# design.net
KiCad netlist of a schematic drawn in Altium Designer
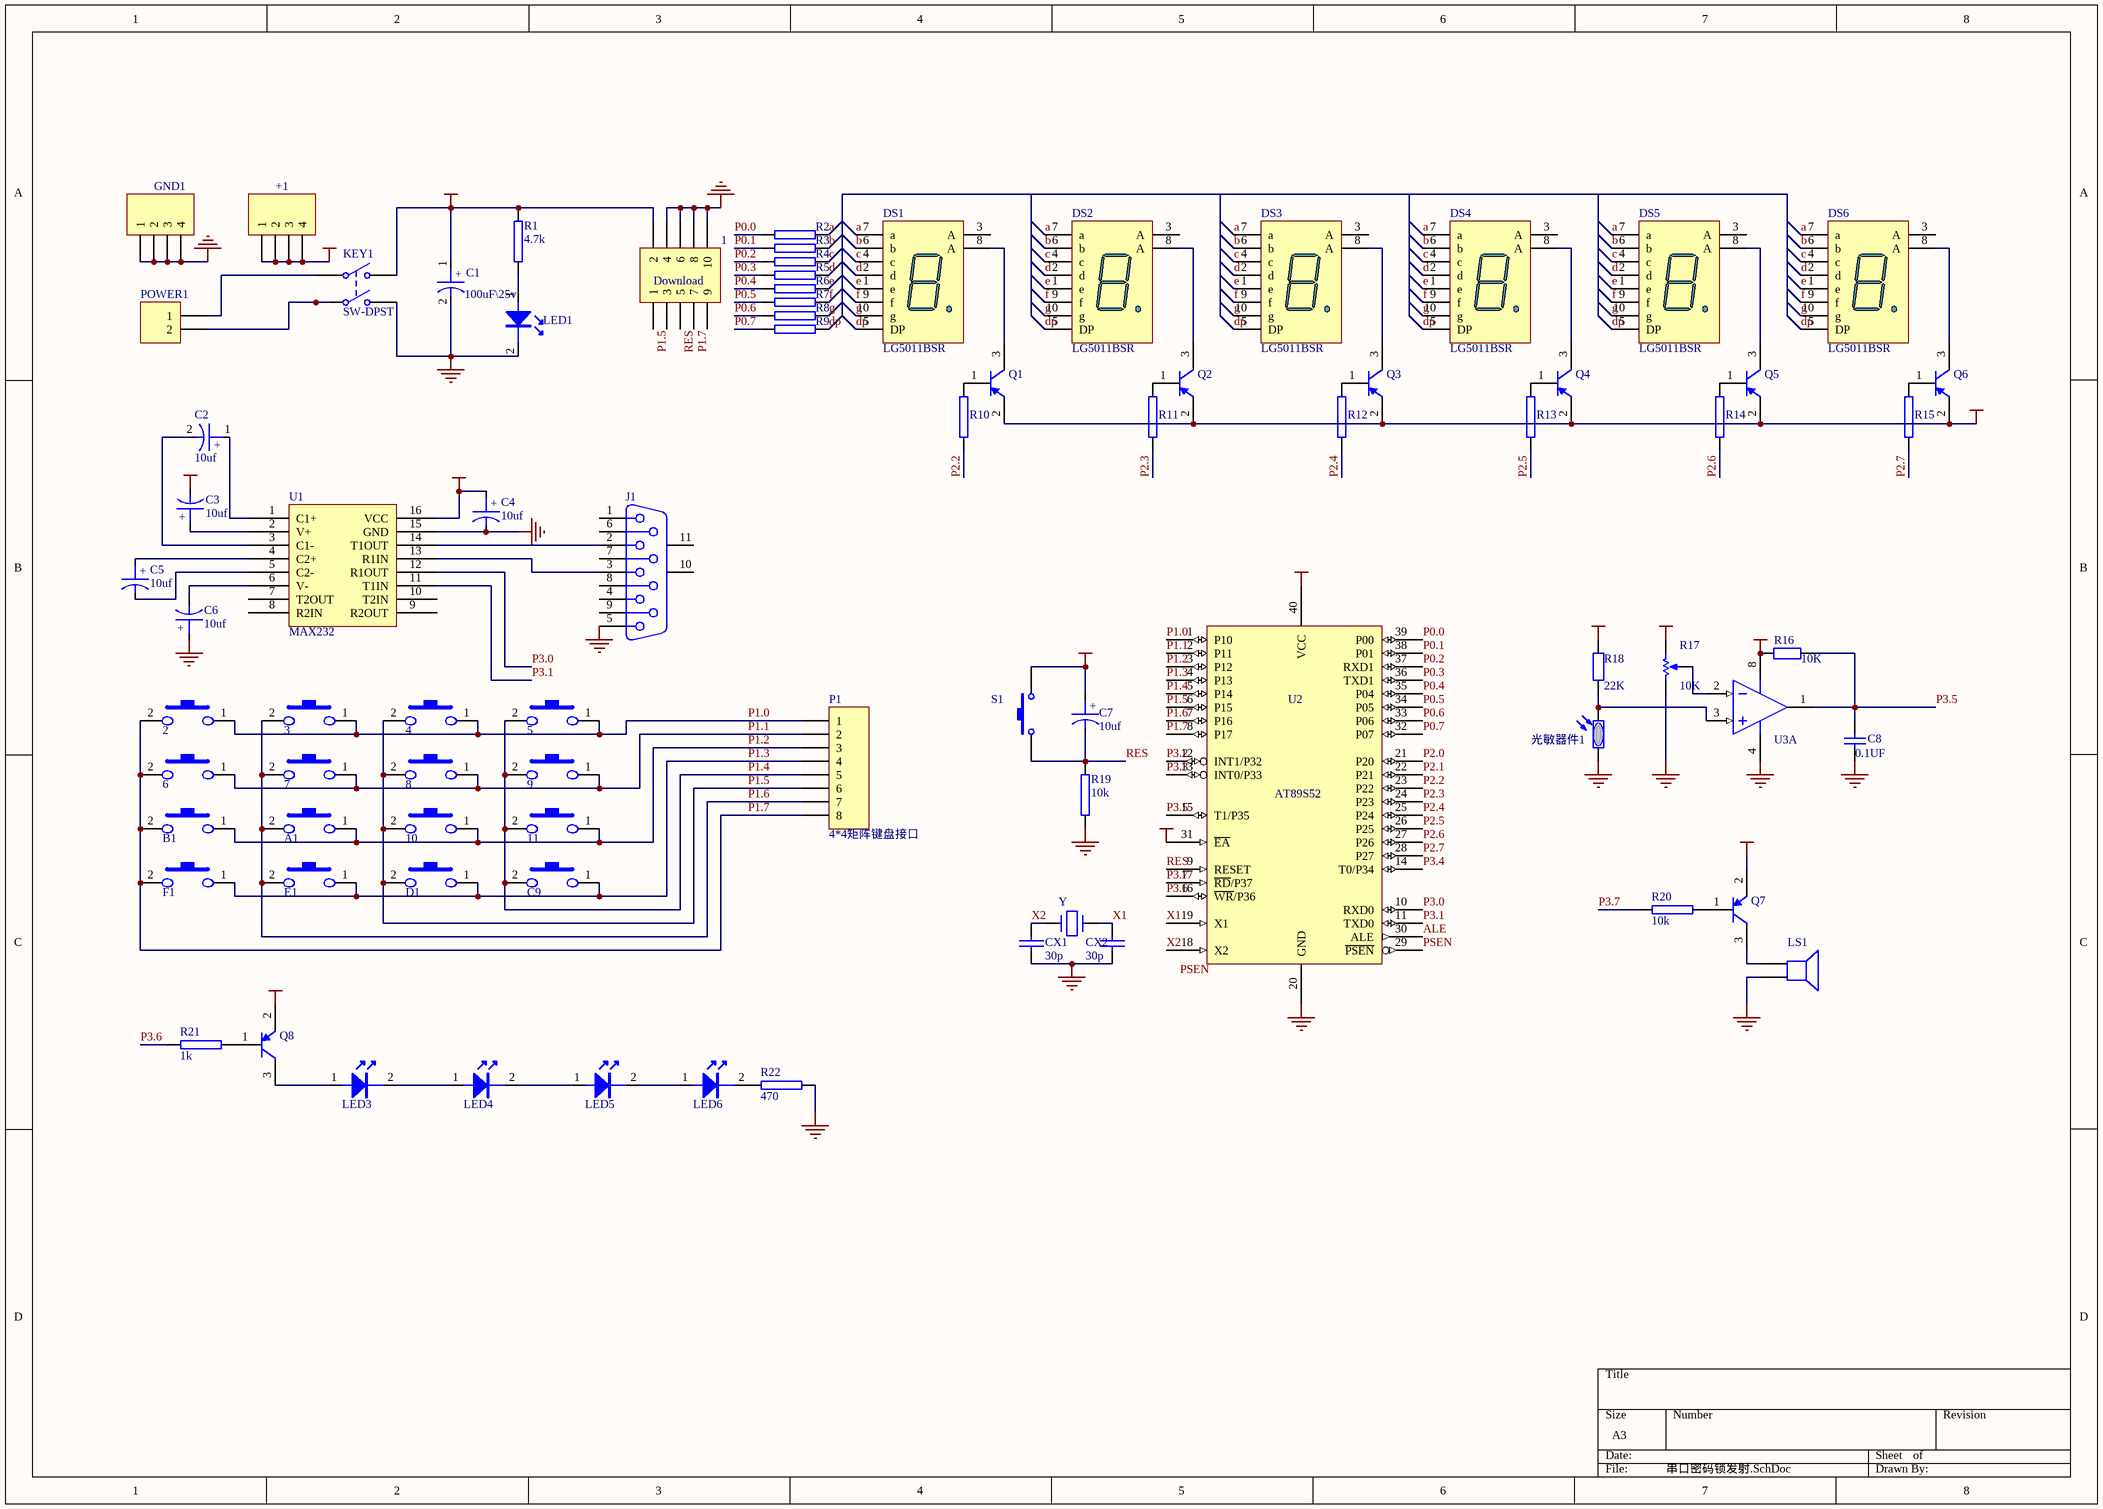
[diagram p0: 串口密码锁发射.SchDoc]

(export (version "E")
  (design (tool "Eeschema 10.0.6"))
  (components
    (comp (ref "+1")
      (value "~")
      (footprint "HDR1X4")
      (description "Header, 4-Pin")
      (fields (field (name "PUBLISHER") "Altium Limited"))
      (libsource (lib "Miscellaneous Connectors") (part "Header 4"))
    )
    (comp (ref "1")
      (value "Download")
      (footprint "HDR-2x5")
      (description "Header, 5-Pin, Dual row")
      (fields (field (name "PUBLISHER") "Altium Limited"))
      (libsource (lib "Miscellaneous Connectors") (part "Header 5X2"))
    )
    (comp (ref "2") (value "key1") (footprint "an-6*6") (libsource (lib "OldCow1 (1)") (part "key")))
    (comp (ref "3") (value "key1") (footprint "an-6*6") (libsource (lib "OldCow1 (1)") (part "key")))
    (comp (ref "4") (value "key1") (footprint "an-6*6") (libsource (lib "OldCow1 (1)") (part "key")))
    (comp (ref "5") (value "key1") (footprint "an-6*6") (libsource (lib "OldCow1 (1)") (part "key")))
    (comp (ref "6") (value "key2") (footprint "an-6*6") (libsource (lib "OldCow1 (1)") (part "key")))
    (comp (ref "7") (value "key2") (footprint "an-6*6") (libsource (lib "OldCow1 (1)") (part "key")))
    (comp (ref "8") (value "key2") (footprint "an-6*6") (libsource (lib "OldCow1 (1)") (part "key")))
    (comp (ref "9") (value "key2") (footprint "an-6*6") (libsource (lib "OldCow1 (1)") (part "key")))
    (comp (ref "10") (value "key3") (footprint "an-6*6") (libsource (lib "OldCow1 (1)") (part "key")))
    (comp (ref "11") (value "key3") (footprint "an-6*6") (libsource (lib "OldCow1 (1)") (part "key")))
    (comp (ref "A1") (value "key3") (footprint "an-6*6") (libsource (lib "OldCow1 (1)") (part "key")))
    (comp (ref "B1") (value "key3") (footprint "an-6*6") (libsource (lib "OldCow1 (1)") (part "key")))
    (comp (ref "C1")
      (value "100u~{F}25v")
      (footprint "C-DJ-6")
      (description "Capacitor")
      (libsource (lib "OldCow1 (1)") (part "CAPACITOR POL"))
    )
    (comp (ref "C2")
      (value "10uf")
      (footprint "C-DJ-4")
      (description "Capacitor")
      (libsource (lib "") (part "CAPACITOR POL_1"))
    )
    (comp (ref "C3")
      (value "10uf")
      (footprint "C-DJ-4")
      (description "Capacitor")
      (libsource (lib "*") (part "CAPACITOR POL"))
    )
    (comp (ref "C4")
      (value "10uf")
      (footprint "C-DJ-4")
      (description "Capacitor")
      (libsource (lib "*") (part "CAPACITOR POL"))
    )
    (comp (ref "C5")
      (value "10uf")
      (footprint "C-DJ-4")
      (description "Capacitor")
      (libsource (lib "*") (part "CAPACITOR POL"))
    )
    (comp (ref "C6")
      (value "10uf")
      (footprint "C-DJ-4")
      (description "Capacitor")
      (libsource (lib "*") (part "CAPACITOR POL"))
    )
    (comp (ref "C7")
      (value "10uf")
      (footprint "C-DJ-4")
      (description "Capacitor")
      (libsource (lib "*") (part "CAPACITOR POL"))
    )
    (comp (ref "C8")
      (value "0.1UF")
      (footprint "C1608-0603")
      (description "Capacitor (Semiconductor SIM Model)")
      (fields (field (name "PUBLISHER") "Altium Limited"))
      (libsource (lib "Miscellaneous Devices") (part "Cap Semi"))
    )
    (comp (ref "C9") (value "key4") (footprint "an-6*6") (libsource (lib "OldCow1 (1)") (part "key")))
    (comp (ref "CX1")
      (value "30p")
      (footprint "HDR1X2")
      (description "Capacitor")
      (libsource (lib "*") (part "CAP"))
    )
    (comp (ref "CX2")
      (value "30p")
      (footprint "HDR1X2")
      (description "Capacitor")
      (libsource (lib "*") (part "CAP"))
    )
    (comp (ref "D1") (value "key4") (footprint "an-6*6") (libsource (lib "OldCow1 (1)") (part "key")))
    (comp (ref "DS1")
      (value "LG5011BSR")
      (footprint "LED-BSR")
      (description "14.2 mm General Purpose Blue 7-Segment Display: CA, RH DP, Gray Surface")
      (fields (field (name "PUBLISHER") "Altium Limited"))
      (libsource (lib "Miscellaneous Devices") (part "Dpy Blue-CA"))
    )
    (comp (ref "DS2")
      (value "LG5011BSR")
      (footprint "LED-BSR")
      (description "14.2 mm General Purpose Blue 7-Segment Display: CA, RH DP, Gray Surface")
      (fields (field (name "PUBLISHER") "Altium Limited"))
      (libsource (lib "Miscellaneous Devices") (part "Dpy Blue-CA"))
    )
    (comp (ref "DS3")
      (value "LG5011BSR")
      (footprint "LED-BSR")
      (description "14.2 mm General Purpose Blue 7-Segment Display: CA, RH DP, Gray Surface")
      (fields (field (name "PUBLISHER") "Altium Limited"))
      (libsource (lib "Miscellaneous Devices") (part "Dpy Blue-CA"))
    )
    (comp (ref "DS4")
      (value "LG5011BSR")
      (footprint "LED-BSR")
      (description "14.2 mm General Purpose Blue 7-Segment Display: CA, RH DP, Gray Surface")
      (fields (field (name "PUBLISHER") "Altium Limited"))
      (libsource (lib "Miscellaneous Devices") (part "Dpy Blue-CA"))
    )
    (comp (ref "DS5")
      (value "LG5011BSR")
      (footprint "LED-BSR")
      (description "14.2 mm General Purpose Blue 7-Segment Display: CA, RH DP, Gray Surface")
      (fields (field (name "PUBLISHER") "Altium Limited"))
      (libsource (lib "Miscellaneous Devices") (part "Dpy Blue-CA"))
    )
    (comp (ref "DS6")
      (value "LG5011BSR")
      (footprint "LED-BSR")
      (description "14.2 mm General Purpose Blue 7-Segment Display: CA, RH DP, Gray Surface")
      (fields (field (name "PUBLISHER") "Altium Limited"))
      (libsource (lib "Miscellaneous Devices") (part "Dpy Blue-CA"))
    )
    (comp (ref "E1") (value "key4") (footprint "an-6*6") (libsource (lib "OldCow1 (1)") (part "key")))
    (comp (ref "F1") (value "key4") (footprint "an-6*6") (libsource (lib "OldCow1 (1)") (part "key")))
    (comp (ref "GND1")
      (value "~")
      (footprint "HDR1X4")
      (description "Header, 4-Pin")
      (fields (field (name "PUBLISHER") "Altium Limited"))
      (libsource (lib "Miscellaneous Connectors") (part "Header 4"))
    )
    (comp (ref "J1")
      (value "D Connector 9")
      (footprint "DSUB1.385-2H9")
      (description "Receptacle Assembly, 9 Position, Right Angle")
      (fields (field (name "PUBLISHER") "Altium Limited"))
      (libsource (lib "Miscellaneous Connectors") (part "D Connector 9"))
    )
    (comp (ref "KEY1")
      (value "SW-DPST")
      (footprint "DPDT-6")
      (description "Double-Pole, Single-Throw Switch")
      (fields (field (name "PUBLISHER") "Altium Limited"))
      (libsource (lib "Miscellaneous Devices") (part "SW-DPST"))
    )
    (comp (ref "LED1") (value "LED") (footprint "LED") (libsource (lib "OldCow1 (1)") (part "LED")))
    (comp (ref "LED3") (value "LED") (footprint "LED") (libsource (lib "OldCow1 (1)") (part "LED")))
    (comp (ref "LED4") (value "LED") (footprint "LED") (libsource (lib "OldCow1 (1)") (part "LED")))
    (comp (ref "LED5") (value "LED") (footprint "LED") (libsource (lib "OldCow1 (1)") (part "LED")))
    (comp (ref "LED6") (value "LED") (footprint "LED") (libsource (lib "OldCow1 (1)") (part "LED")))
    (comp (ref "LS1")
      (value "~")
      (footprint "LS1PF")
      (description "Loudspeaker")
      (fields (field (name "PUBLISHER") "Altium Limited"))
      (libsource (lib "Miscellaneous Devices") (part "Speaker"))
    )
    (comp (ref "P1")
      (value "4*4矩阵键盘接口")
      (footprint "HDR1X8")
      (description "Header, 8-Pin")
      (fields (field (name "PUBLISHER") "Altium Limited"))
      (libsource (lib "Miscellaneous Connectors") (part "Header 8"))
    )
    (comp (ref "POWER1")
      (value "~")
      (footprint "JK128")
      (description "Header, 2-Pin")
      (fields (field (name "PUBLISHER") "Altium Limited"))
      (libsource (lib "Miscellaneous Connectors") (part "Header 2"))
    )
    (comp (ref "Q1")
      (value "2N3906")
      (footprint "SO-G3")
      (description "PNP General Purpose Amplifier")
      (fields (field (name "PUBLISHER") "Altium Limited"))
      (libsource (lib "Miscellaneous Devices") (part "2N3906"))
    )
    (comp (ref "Q2")
      (value "2N3906")
      (footprint "SO-G3")
      (description "PNP General Purpose Amplifier")
      (fields (field (name "PUBLISHER") "Altium Limited"))
      (libsource (lib "Miscellaneous Devices") (part "2N3906"))
    )
    (comp (ref "Q3")
      (value "2N3906")
      (footprint "SO-G3")
      (description "PNP General Purpose Amplifier")
      (fields (field (name "PUBLISHER") "Altium Limited"))
      (libsource (lib "Miscellaneous Devices") (part "2N3906"))
    )
    (comp (ref "Q4")
      (value "2N3906")
      (footprint "SO-G3")
      (description "PNP General Purpose Amplifier")
      (fields (field (name "PUBLISHER") "Altium Limited"))
      (libsource (lib "Miscellaneous Devices") (part "2N3906"))
    )
    (comp (ref "Q5")
      (value "2N3906")
      (footprint "SO-G3")
      (description "PNP General Purpose Amplifier")
      (fields (field (name "PUBLISHER") "Altium Limited"))
      (libsource (lib "Miscellaneous Devices") (part "2N3906"))
    )
    (comp (ref "Q6")
      (value "2N3906")
      (footprint "SO-G3")
      (description "PNP General Purpose Amplifier")
      (fields (field (name "PUBLISHER") "Altium Limited"))
      (libsource (lib "Miscellaneous Devices") (part "2N3906"))
    )
    (comp (ref "Q7")
      (value "2N3906")
      (footprint "SO-G3")
      (description "PNP General Purpose Amplifier")
      (fields (field (name "PUBLISHER") "Altium Limited"))
      (libsource (lib "Miscellaneous Devices") (part "2N3906"))
    )
    (comp (ref "Q8")
      (value "2N3906")
      (footprint "SO-G3")
      (description "PNP General Purpose Amplifier")
      (fields (field (name "PUBLISHER") "Altium Limited"))
      (libsource (lib "Miscellaneous Devices") (part "2N3906"))
    )
    (comp (ref "R1") (value "4.7k") (footprint "R2012-0805") (libsource (lib "*") (part "RES2")))
    (comp (ref "R2") (value "470") (footprint "R2012-0805") (libsource (lib "*") (part "RES2")))
    (comp (ref "R3") (value "470") (footprint "R2012-0805") (libsource (lib "*") (part "RES2")))
    (comp (ref "R4") (value "470") (footprint "R2012-0805") (libsource (lib "*") (part "RES2")))
    (comp (ref "R5") (value "470") (footprint "R2012-0805") (libsource (lib "*") (part "RES2")))
    (comp (ref "R6") (value "470") (footprint "R2012-0805") (libsource (lib "*") (part "RES2")))
    (comp (ref "R7") (value "470") (footprint "R2012-0805") (libsource (lib "*") (part "RES2")))
    (comp (ref "R8") (value "470") (footprint "R2012-0805") (libsource (lib "*") (part "RES2")))
    (comp (ref "R9") (value "470") (footprint "R2012-0805") (libsource (lib "*") (part "RES2")))
    (comp (ref "R10") (value "470") (footprint "R2012-0805") (libsource (lib "*") (part "RES2")))
    (comp (ref "R11") (value "470") (footprint "R2012-0805") (libsource (lib "*") (part "RES2")))
    (comp (ref "R12") (value "470") (footprint "R2012-0805") (libsource (lib "*") (part "RES2")))
    (comp (ref "R13") (value "470") (footprint "R2012-0805") (libsource (lib "*") (part "RES2")))
    (comp (ref "R14") (value "470") (footprint "R2012-0805") (libsource (lib "*") (part "RES2")))
    (comp (ref "R15") (value "470") (footprint "R2012-0805") (libsource (lib "*") (part "RES2")))
    (comp (ref "R16")
      (value "10K")
      (footprint "C1608-0603")
      (description "Resistor")
      (fields (field (name "PUBLISHER") "Altium Limited"))
      (libsource (lib "Miscellaneous Devices") (part "Res2"))
    )
    (comp (ref "R17")
      (value "10K")
      (footprint "HDR1X3")
      (description "Potentiometer")
      (fields (field (name "PUBLISHER") "Altium Limited"))
      (libsource (lib "Miscellaneous Devices") (part "RPot"))
    )
    (comp (ref "R18")
      (value "22K")
      (footprint "C1608-0603")
      (description "Resistor")
      (fields (field (name "PUBLISHER") "Altium Limited"))
      (libsource (lib "") (part "Res2_1"))
    )
    (comp (ref "R19") (value "10k") (footprint "R2012-0805") (libsource (lib "*") (part "RES2")))
    (comp (ref "R20") (value "10k") (footprint "R2012-0805") (libsource (lib "*") (part "RES2")))
    (comp (ref "R21") (value "1k") (footprint "R2012-0805") (libsource (lib "*") (part "RES2")))
    (comp (ref "R22") (value "470") (footprint "R2012-0805") (libsource (lib "*") (part "RES2")))
    (comp (ref "S1")
      (value "~")
      (footprint "an-6*6")
      (description "Switch")
      (fields (field (name "PUBLISHER") "Altium Limited"))
      (libsource (lib "Miscellaneous Devices") (part "SW-PB"))
    )
    (comp (ref "U1") (value "MAX232") (footprint "DIP16") (libsource (lib "*") (part "MAX232")))
    (comp (ref "U2") (value "AT89S52") (footprint "AT89S52Pid") (libsource (lib "OldCow1 (2)") (part "8051")))
    (comp (ref "U3")
      (value "~")
      (footprint "SO8")
      (description "Low-Power Dual Voltage Comparator")
      (fields (field (name "PUBLISHER") "Altium Limited"))
      (libsource (lib "ST Analog Comparator") (part "LM393AD"))
    )
    (comp (ref "Y1")
      (value "Y")
      (footprint "11.0592M")
      (description "Crystal")
      (libsource (lib "*") (part "CRYSTAL"))
    )
    (comp (ref "光敏器件1")
      (value "~")
      (footprint "PIN2")
      (description "光敏阻性器件")
      (fields (field (name "PUBLISHER") "Altium Limited"))
      (libsource (lib "zxcourhc") (part "GMDZ"))
    )
  )
  (nets
    (net (code "1") (name "/ALE") (class "Default")
      (node (ref "U2") (pin "30") (pinfunction "ALE_30") (pintype "output"))
    )
    (net (code "2") (name "/P0.0") (class "Default")
      (node (ref "R2") (pin "1") (pinfunction "1_1") (pintype "passive"))
      (node (ref "U2") (pin "39") (pinfunction "P00_39") (pintype "bidirectional"))
    )
    (net (code "3") (name "/P0.1") (class "Default")
      (node (ref "R3") (pin "1") (pinfunction "1_1") (pintype "passive"))
      (node (ref "U2") (pin "38") (pinfunction "P01_38") (pintype "bidirectional"))
    )
    (net (code "4") (name "/P0.2") (class "Default")
      (node (ref "R4") (pin "1") (pinfunction "1_1") (pintype "passive"))
      (node (ref "U2") (pin "37") (pinfunction "RXD1_37") (pintype "bidirectional"))
    )
    (net (code "5") (name "/P0.3") (class "Default")
      (node (ref "R5") (pin "1") (pinfunction "1_1") (pintype "passive"))
      (node (ref "U2") (pin "36") (pinfunction "TXD1_36") (pintype "bidirectional"))
    )
    (net (code "6") (name "/P0.4") (class "Default")
      (node (ref "R6") (pin "1") (pinfunction "1_1") (pintype "passive"))
      (node (ref "U2") (pin "35") (pinfunction "P04_35") (pintype "bidirectional"))
    )
    (net (code "7") (name "/P0.5") (class "Default")
      (node (ref "R7") (pin "1") (pinfunction "1_1") (pintype "passive"))
      (node (ref "U2") (pin "34") (pinfunction "P05_34") (pintype "bidirectional"))
    )
    (net (code "8") (name "/P0.6") (class "Default")
      (node (ref "R8") (pin "1") (pinfunction "1_1") (pintype "passive"))
      (node (ref "U2") (pin "33") (pinfunction "P06_33") (pintype "bidirectional"))
    )
    (net (code "9") (name "/P0.7") (class "Default")
      (node (ref "R9") (pin "1") (pinfunction "1_1") (pintype "passive"))
      (node (ref "U2") (pin "32") (pinfunction "P07_32") (pintype "bidirectional"))
    )
    (net (code "10") (name "/P1.0") (class "Default")
      (node (ref "2") (pin "1") (pinfunction "1_1") (pintype "passive"))
      (node (ref "3") (pin "1") (pinfunction "1_1") (pintype "passive"))
      (node (ref "4") (pin "1") (pinfunction "1_1") (pintype "passive"))
      (node (ref "5") (pin "1") (pinfunction "1_1") (pintype "passive"))
      (node (ref "P1") (pin "1") (pinfunction "1_1") (pintype "passive"))
      (node (ref "U2") (pin "1") (pinfunction "P10_1") (pintype "bidirectional"))
    )
    (net (code "11") (name "/P1.1") (class "Default")
      (node (ref "6") (pin "1") (pinfunction "1_1") (pintype "passive"))
      (node (ref "7") (pin "1") (pinfunction "1_1") (pintype "passive"))
      (node (ref "8") (pin "1") (pinfunction "1_1") (pintype "passive"))
      (node (ref "9") (pin "1") (pinfunction "1_1") (pintype "passive"))
      (node (ref "P1") (pin "2") (pinfunction "2_2") (pintype "passive"))
      (node (ref "U2") (pin "2") (pinfunction "P11_2") (pintype "bidirectional"))
    )
    (net (code "12") (name "/P1.2") (class "Default")
      (node (ref "10") (pin "1") (pinfunction "1_1") (pintype "passive"))
      (node (ref "11") (pin "1") (pinfunction "1_1") (pintype "passive"))
      (node (ref "A1") (pin "1") (pinfunction "1_1") (pintype "passive"))
      (node (ref "B1") (pin "1") (pinfunction "1_1") (pintype "passive"))
      (node (ref "P1") (pin "3") (pinfunction "3_3") (pintype "passive"))
      (node (ref "U2") (pin "3") (pinfunction "P12_3") (pintype "bidirectional"))
    )
    (net (code "13") (name "/P1.3") (class "Default")
      (node (ref "C9") (pin "1") (pinfunction "1_1") (pintype "passive"))
      (node (ref "D1") (pin "1") (pinfunction "1_1") (pintype "passive"))
      (node (ref "E1") (pin "1") (pinfunction "1_1") (pintype "passive"))
      (node (ref "F1") (pin "1") (pinfunction "1_1") (pintype "passive"))
      (node (ref "P1") (pin "4") (pinfunction "4_4") (pintype "passive"))
      (node (ref "U2") (pin "4") (pinfunction "P13_4") (pintype "bidirectional"))
    )
    (net (code "14") (name "/P1.4") (class "Default")
      (node (ref "11") (pin "2") (pinfunction "2_2") (pintype "passive"))
      (node (ref "5") (pin "2") (pinfunction "2_2") (pintype "passive"))
      (node (ref "9") (pin "2") (pinfunction "2_2") (pintype "passive"))
      (node (ref "C9") (pin "2") (pinfunction "2_2") (pintype "passive"))
      (node (ref "P1") (pin "5") (pinfunction "5_5") (pintype "passive"))
      (node (ref "U2") (pin "5") (pinfunction "P14_5") (pintype "bidirectional"))
    )
    (net (code "15") (name "/P1.5") (class "Default")
      (node (ref "1") (pin "1") (pinfunction "1_1") (pintype "passive"))
      (node (ref "10") (pin "2") (pinfunction "2_2") (pintype "passive"))
      (node (ref "4") (pin "2") (pinfunction "2_2") (pintype "passive"))
      (node (ref "8") (pin "2") (pinfunction "2_2") (pintype "passive"))
      (node (ref "D1") (pin "2") (pinfunction "2_2") (pintype "passive"))
      (node (ref "P1") (pin "6") (pinfunction "6_6") (pintype "passive"))
      (node (ref "U2") (pin "6") (pinfunction "P15_6") (pintype "bidirectional"))
    )
    (net (code "16") (name "/P1.6") (class "Default")
      (node (ref "3") (pin "2") (pinfunction "2_2") (pintype "passive"))
      (node (ref "7") (pin "2") (pinfunction "2_2") (pintype "passive"))
      (node (ref "A1") (pin "2") (pinfunction "2_2") (pintype "passive"))
      (node (ref "E1") (pin "2") (pinfunction "2_2") (pintype "passive"))
      (node (ref "P1") (pin "7") (pinfunction "7_7") (pintype "passive"))
      (node (ref "U2") (pin "7") (pinfunction "P16_7") (pintype "bidirectional"))
    )
    (net (code "17") (name "/P1.7") (class "Default")
      (node (ref "1") (pin "7") (pinfunction "7_7") (pintype "passive"))
      (node (ref "2") (pin "2") (pinfunction "2_2") (pintype "passive"))
      (node (ref "6") (pin "2") (pinfunction "2_2") (pintype "passive"))
      (node (ref "B1") (pin "2") (pinfunction "2_2") (pintype "passive"))
      (node (ref "F1") (pin "2") (pinfunction "2_2") (pintype "passive"))
      (node (ref "P1") (pin "8") (pinfunction "8_8") (pintype "passive"))
      (node (ref "U2") (pin "8") (pinfunction "P17_8") (pintype "bidirectional"))
    )
    (net (code "18") (name "/P2.0") (class "Default")
      (node (ref "U2") (pin "21") (pinfunction "P20_21") (pintype "bidirectional"))
    )
    (net (code "19") (name "/P2.1") (class "Default")
      (node (ref "U2") (pin "22") (pinfunction "P21_22") (pintype "bidirectional"))
    )
    (net (code "20") (name "/P2.2") (class "Default")
      (node (ref "R10") (pin "1") (pinfunction "1_1") (pintype "passive"))
      (node (ref "U2") (pin "23") (pinfunction "P22_23") (pintype "bidirectional"))
    )
    (net (code "21") (name "/P2.3") (class "Default")
      (node (ref "R11") (pin "1") (pinfunction "1_1") (pintype "passive"))
      (node (ref "U2") (pin "24") (pinfunction "P23_24") (pintype "bidirectional"))
    )
    (net (code "22") (name "/P2.4") (class "Default")
      (node (ref "R12") (pin "1") (pinfunction "1_1") (pintype "passive"))
      (node (ref "U2") (pin "25") (pinfunction "P24_25") (pintype "bidirectional"))
    )
    (net (code "23") (name "/P2.5") (class "Default")
      (node (ref "R13") (pin "1") (pinfunction "1_1") (pintype "passive"))
      (node (ref "U2") (pin "26") (pinfunction "P25_26") (pintype "bidirectional"))
    )
    (net (code "24") (name "/P2.6") (class "Default")
      (node (ref "R14") (pin "1") (pinfunction "1_1") (pintype "passive"))
      (node (ref "U2") (pin "27") (pinfunction "P26_27") (pintype "bidirectional"))
    )
    (net (code "25") (name "/P2.7") (class "Default")
      (node (ref "R15") (pin "1") (pinfunction "1_1") (pintype "passive"))
      (node (ref "U2") (pin "28") (pinfunction "P27_28") (pintype "bidirectional"))
    )
    (net (code "26") (name "/P3.0") (class "Default")
      (node (ref "U1") (pin "12") (pinfunction "R1OUT_12") (pintype "passive"))
      (node (ref "U2") (pin "10") (pinfunction "RXD0_10") (pintype "bidirectional"))
    )
    (net (code "27") (name "/P3.1") (class "Default")
      (node (ref "U1") (pin "11") (pinfunction "T1IN_11") (pintype "passive"))
      (node (ref "U2") (pin "11") (pinfunction "TXD0_11") (pintype "bidirectional"))
    )
    (net (code "28") (name "/P3.2") (class "Default")
      (node (ref "U2") (pin "12") (pinfunction "INT1/P32_12") (pintype "bidirectional"))
    )
    (net (code "29") (name "/P3.3") (class "Default")
      (node (ref "U2") (pin "13") (pinfunction "INT0/P33_13") (pintype "bidirectional"))
    )
    (net (code "30") (name "/P3.4") (class "Default")
      (node (ref "U2") (pin "14") (pinfunction "T0/P34_14") (pintype "bidirectional"))
    )
    (net (code "31") (name "/P3.5") (class "Default")
      (node (ref "C8") (pin "2") (pinfunction "2_2") (pintype "passive"))
      (node (ref "R16") (pin "1") (pinfunction "1_1") (pintype "passive"))
      (node (ref "U2") (pin "15") (pinfunction "T1/P35_15") (pintype "bidirectional"))
      (node (ref "U3") (pin "1") (pinfunction "OUT_1") (pintype "open_collector"))
    )
    (net (code "32") (name "/P3.6") (class "Default")
      (node (ref "R21") (pin "1") (pinfunction "1_1") (pintype "passive"))
      (node (ref "U2") (pin "16") (pinfunction "~{WR}/P36_16") (pintype "bidirectional"))
    )
    (net (code "33") (name "/P3.7") (class "Default")
      (node (ref "R20") (pin "1") (pinfunction "1_1") (pintype "passive"))
      (node (ref "U2") (pin "17") (pinfunction "~{RD}/P37_17") (pintype "input"))
    )
    (net (code "34") (name "/PSEN") (class "Default")
      (node (ref "U2") (pin "29") (pinfunction "~{PSEN}_29") (pintype "output"))
    )
    (net (code "35") (name "/RES") (class "Default")
      (node (ref "1") (pin "5") (pinfunction "5_5") (pintype "passive"))
      (node (ref "C7") (pin "2") (pinfunction "2_2") (pintype "passive"))
      (node (ref "R19") (pin "1") (pinfunction "1_1") (pintype "passive"))
      (node (ref "S1") (pin "1") (pinfunction "1_1") (pintype "passive"))
      (node (ref "U2") (pin "9") (pinfunction "RESET_9") (pintype "input"))
    )
    (net (code "36") (name "/X1") (class "Default")
      (node (ref "CX2") (pin "1") (pinfunction "1_1") (pintype "passive"))
      (node (ref "U2") (pin "19") (pinfunction "X1_19") (pintype "input"))
      (node (ref "Y1") (pin "1") (pinfunction "1_1") (pintype "passive"))
    )
    (net (code "37") (name "/X2") (class "Default")
      (node (ref "CX1") (pin "1") (pinfunction "1_1") (pintype "passive"))
      (node (ref "U2") (pin "18") (pinfunction "X2_18") (pintype "input"))
      (node (ref "Y1") (pin "2") (pinfunction "2_2") (pintype "passive"))
    )
    (net (code "38") (name "/a") (class "Default")
      (node (ref "DS1") (pin "7") (pinfunction "a_7") (pintype "passive"))
      (node (ref "DS2") (pin "7") (pinfunction "a_7") (pintype "passive"))
      (node (ref "DS3") (pin "7") (pinfunction "a_7") (pintype "passive"))
      (node (ref "DS4") (pin "7") (pinfunction "a_7") (pintype "passive"))
      (node (ref "DS5") (pin "7") (pinfunction "a_7") (pintype "passive"))
      (node (ref "DS6") (pin "7") (pinfunction "a_7") (pintype "passive"))
      (node (ref "R2") (pin "2") (pinfunction "2_2") (pintype "passive"))
    )
    (net (code "39") (name "/b") (class "Default")
      (node (ref "DS1") (pin "6") (pinfunction "b_6") (pintype "passive"))
      (node (ref "DS2") (pin "6") (pinfunction "b_6") (pintype "passive"))
      (node (ref "DS3") (pin "6") (pinfunction "b_6") (pintype "passive"))
      (node (ref "DS4") (pin "6") (pinfunction "b_6") (pintype "passive"))
      (node (ref "DS5") (pin "6") (pinfunction "b_6") (pintype "passive"))
      (node (ref "DS6") (pin "6") (pinfunction "b_6") (pintype "passive"))
      (node (ref "R3") (pin "2") (pinfunction "2_2") (pintype "passive"))
    )
    (net (code "40") (name "/c") (class "Default")
      (node (ref "DS1") (pin "4") (pinfunction "c_4") (pintype "passive"))
      (node (ref "DS2") (pin "4") (pinfunction "c_4") (pintype "passive"))
      (node (ref "DS3") (pin "4") (pinfunction "c_4") (pintype "passive"))
      (node (ref "DS4") (pin "4") (pinfunction "c_4") (pintype "passive"))
      (node (ref "DS5") (pin "4") (pinfunction "c_4") (pintype "passive"))
      (node (ref "DS6") (pin "4") (pinfunction "c_4") (pintype "passive"))
      (node (ref "R4") (pin "2") (pinfunction "2_2") (pintype "passive"))
    )
    (net (code "41") (name "/d") (class "Default")
      (node (ref "DS1") (pin "2") (pinfunction "d_2") (pintype "passive"))
      (node (ref "DS2") (pin "2") (pinfunction "d_2") (pintype "passive"))
      (node (ref "DS3") (pin "2") (pinfunction "d_2") (pintype "passive"))
      (node (ref "DS4") (pin "2") (pinfunction "d_2") (pintype "passive"))
      (node (ref "DS5") (pin "2") (pinfunction "d_2") (pintype "passive"))
      (node (ref "DS6") (pin "2") (pinfunction "d_2") (pintype "passive"))
      (node (ref "R5") (pin "2") (pinfunction "2_2") (pintype "passive"))
    )
    (net (code "42") (name "/dp") (class "Default")
      (node (ref "DS1") (pin "5") (pinfunction "DP_5") (pintype "passive"))
      (node (ref "DS2") (pin "5") (pinfunction "DP_5") (pintype "passive"))
      (node (ref "DS3") (pin "5") (pinfunction "DP_5") (pintype "passive"))
      (node (ref "DS4") (pin "5") (pinfunction "DP_5") (pintype "passive"))
      (node (ref "DS5") (pin "5") (pinfunction "DP_5") (pintype "passive"))
      (node (ref "DS6") (pin "5") (pinfunction "DP_5") (pintype "passive"))
      (node (ref "R9") (pin "2") (pinfunction "2_2") (pintype "passive"))
    )
    (net (code "43") (name "/e") (class "Default")
      (node (ref "DS1") (pin "1") (pinfunction "e_1") (pintype "passive"))
      (node (ref "DS2") (pin "1") (pinfunction "e_1") (pintype "passive"))
      (node (ref "DS3") (pin "1") (pinfunction "e_1") (pintype "passive"))
      (node (ref "DS4") (pin "1") (pinfunction "e_1") (pintype "passive"))
      (node (ref "DS5") (pin "1") (pinfunction "e_1") (pintype "passive"))
      (node (ref "DS6") (pin "1") (pinfunction "e_1") (pintype "passive"))
      (node (ref "R6") (pin "2") (pinfunction "2_2") (pintype "passive"))
    )
    (net (code "44") (name "/f") (class "Default")
      (node (ref "DS1") (pin "9") (pinfunction "f_9") (pintype "passive"))
      (node (ref "DS2") (pin "9") (pinfunction "f_9") (pintype "passive"))
      (node (ref "DS3") (pin "9") (pinfunction "f_9") (pintype "passive"))
      (node (ref "DS4") (pin "9") (pinfunction "f_9") (pintype "passive"))
      (node (ref "DS5") (pin "9") (pinfunction "f_9") (pintype "passive"))
      (node (ref "DS6") (pin "9") (pinfunction "f_9") (pintype "passive"))
      (node (ref "R7") (pin "2") (pinfunction "2_2") (pintype "passive"))
    )
    (net (code "45") (name "/g") (class "Default")
      (node (ref "DS1") (pin "10") (pinfunction "g_10") (pintype "passive"))
      (node (ref "DS2") (pin "10") (pinfunction "g_10") (pintype "passive"))
      (node (ref "DS3") (pin "10") (pinfunction "g_10") (pintype "passive"))
      (node (ref "DS4") (pin "10") (pinfunction "g_10") (pintype "passive"))
      (node (ref "DS5") (pin "10") (pinfunction "g_10") (pintype "passive"))
      (node (ref "DS6") (pin "10") (pinfunction "g_10") (pintype "passive"))
      (node (ref "R8") (pin "2") (pinfunction "2_2") (pintype "passive"))
    )
    (net (code "46") (name "GND") (class "Default")
      (node (ref "1") (pin "10") (pinfunction "10_10") (pintype "passive"))
      (node (ref "1") (pin "4") (pinfunction "4_4") (pintype "passive"))
      (node (ref "1") (pin "6") (pinfunction "6_6") (pintype "passive"))
      (node (ref "1") (pin "8") (pinfunction "8_8") (pintype "passive"))
      (node (ref "C1") (pin "2") (pinfunction "2_2") (pintype "passive"))
      (node (ref "C4") (pin "2") (pinfunction "2_2") (pintype "passive"))
      (node (ref "C6") (pin "1") (pinfunction "1_1") (pintype "passive"))
      (node (ref "C8") (pin "1") (pinfunction "1_1") (pintype "passive"))
      (node (ref "CX1") (pin "2") (pinfunction "2_2") (pintype "passive"))
      (node (ref "CX2") (pin "2") (pinfunction "2_2") (pintype "passive"))
      (node (ref "GND1") (pin "1") (pinfunction "1_1") (pintype "passive"))
      (node (ref "GND1") (pin "2") (pinfunction "2_2") (pintype "passive"))
      (node (ref "GND1") (pin "3") (pinfunction "3_3") (pintype "passive"))
      (node (ref "GND1") (pin "4") (pinfunction "4_4") (pintype "passive"))
      (node (ref "J1") (pin "5") (pinfunction "5_5") (pintype "passive"))
      (node (ref "KEY1") (pin "4") (pinfunction "NO2_4") (pintype "passive"))
      (node (ref "LED1") (pin "2") (pinfunction "K_2") (pintype "passive"))
      (node (ref "LS1") (pin "2") (pinfunction "2_2") (pintype "passive"))
      (node (ref "R17") (pin "2") (pinfunction "BOT_2") (pintype "passive"))
      (node (ref "R19") (pin "2") (pinfunction "2_2") (pintype "passive"))
      (node (ref "R22") (pin "2") (pinfunction "2_2") (pintype "passive"))
      (node (ref "U1") (pin "15") (pinfunction "GND_15") (pintype "passive"))
      (node (ref "U2") (pin "20") (pinfunction "GND_20") (pintype "power_in"))
      (node (ref "U3") (pin "4") (pinfunction "V-_4") (pintype "power_in"))
      (node (ref "光敏器件1") (pin "2") (pinfunction "2_2") (pintype "passive"))
    )
    (net (code "47") (name "Net-(KEY1-COMMON1)") (class "Default")
      (node (ref "KEY1") (pin "1") (pinfunction "COMMON1_1") (pintype "passive"))
      (node (ref "POWER1") (pin "1") (pinfunction "1_1") (pintype "passive"))
    )
    (net (code "48") (name "Net-(KEY1-COMMON2)") (class "Default")
      (node (ref "KEY1") (pin "3") (pinfunction "COMMON2_3") (pintype "passive"))
      (node (ref "POWER1") (pin "2") (pinfunction "2_2") (pintype "passive"))
    )
    (net (code "49") (name "Net-(LED1-A)") (class "Default")
      (node (ref "LED1") (pin "1") (pinfunction "A_1") (pintype "passive"))
      (node (ref "R1") (pin "2") (pinfunction "2_2") (pintype "passive"))
    )
    (net (code "50") (name "Net-(LED3-A)") (class "Default")
      (node (ref "LED3") (pin "1") (pinfunction "A_1") (pintype "passive"))
      (node (ref "Q8") (pin "3") (pinfunction "C_3") (pintype "passive"))
    )
    (net (code "51") (name "Net-(LED3-K)") (class "Default")
      (node (ref "LED3") (pin "2") (pinfunction "K_2") (pintype "passive"))
      (node (ref "LED4") (pin "1") (pinfunction "A_1") (pintype "passive"))
    )
    (net (code "52") (name "Net-(LED4-K)") (class "Default")
      (node (ref "LED4") (pin "2") (pinfunction "K_2") (pintype "passive"))
      (node (ref "LED5") (pin "1") (pinfunction "A_1") (pintype "passive"))
    )
    (net (code "53") (name "Net-(LED5-K)") (class "Default")
      (node (ref "LED5") (pin "2") (pinfunction "K_2") (pintype "passive"))
      (node (ref "LED6") (pin "1") (pinfunction "A_1") (pintype "passive"))
    )
    (net (code "54") (name "Net-(LED6-K)") (class "Default")
      (node (ref "LED6") (pin "2") (pinfunction "K_2") (pintype "passive"))
      (node (ref "R22") (pin "1") (pinfunction "1_1") (pintype "passive"))
    )
    (net (code "55") (name "Net-(Q1-B)") (class "Default")
      (node (ref "Q1") (pin "1") (pinfunction "B_1") (pintype "passive"))
      (node (ref "R10") (pin "2") (pinfunction "2_2") (pintype "passive"))
    )
    (net (code "56") (name "Net-(Q1-C)") (class "Default")
      (node (ref "DS1") (pin "8") (pinfunction "A_8") (pintype "passive"))
      (node (ref "Q1") (pin "3") (pinfunction "C_3") (pintype "passive"))
    )
    (net (code "57") (name "Net-(Q2-B)") (class "Default")
      (node (ref "Q2") (pin "1") (pinfunction "B_1") (pintype "passive"))
      (node (ref "R11") (pin "2") (pinfunction "2_2") (pintype "passive"))
    )
    (net (code "58") (name "Net-(Q2-C)") (class "Default")
      (node (ref "DS2") (pin "8") (pinfunction "A_8") (pintype "passive"))
      (node (ref "Q2") (pin "3") (pinfunction "C_3") (pintype "passive"))
    )
    (net (code "59") (name "Net-(Q3-B)") (class "Default")
      (node (ref "Q3") (pin "1") (pinfunction "B_1") (pintype "passive"))
      (node (ref "R12") (pin "2") (pinfunction "2_2") (pintype "passive"))
    )
    (net (code "60") (name "Net-(Q3-C)") (class "Default")
      (node (ref "DS3") (pin "8") (pinfunction "A_8") (pintype "passive"))
      (node (ref "Q3") (pin "3") (pinfunction "C_3") (pintype "passive"))
    )
    (net (code "61") (name "Net-(Q4-B)") (class "Default")
      (node (ref "Q4") (pin "1") (pinfunction "B_1") (pintype "passive"))
      (node (ref "R13") (pin "2") (pinfunction "2_2") (pintype "passive"))
    )
    (net (code "62") (name "Net-(Q4-C)") (class "Default")
      (node (ref "DS4") (pin "8") (pinfunction "A_8") (pintype "passive"))
      (node (ref "Q4") (pin "3") (pinfunction "C_3") (pintype "passive"))
    )
    (net (code "63") (name "Net-(Q5-B)") (class "Default")
      (node (ref "Q5") (pin "1") (pinfunction "B_1") (pintype "passive"))
      (node (ref "R14") (pin "2") (pinfunction "2_2") (pintype "passive"))
    )
    (net (code "64") (name "Net-(Q5-C)") (class "Default")
      (node (ref "DS5") (pin "8") (pinfunction "A_8") (pintype "passive"))
      (node (ref "Q5") (pin "3") (pinfunction "C_3") (pintype "passive"))
    )
    (net (code "65") (name "Net-(Q6-B)") (class "Default")
      (node (ref "Q6") (pin "1") (pinfunction "B_1") (pintype "passive"))
      (node (ref "R15") (pin "2") (pinfunction "2_2") (pintype "passive"))
    )
    (net (code "66") (name "Net-(Q6-C)") (class "Default")
      (node (ref "DS6") (pin "8") (pinfunction "A_8") (pintype "passive"))
      (node (ref "Q6") (pin "3") (pinfunction "C_3") (pintype "passive"))
    )
    (net (code "67") (name "Net-(Q7-B)") (class "Default")
      (node (ref "Q7") (pin "1") (pinfunction "B_1") (pintype "passive"))
      (node (ref "R20") (pin "2") (pinfunction "2_2") (pintype "passive"))
    )
    (net (code "68") (name "Net-(Q7-C)") (class "Default")
      (node (ref "LS1") (pin "1") (pinfunction "1_1") (pintype "passive"))
      (node (ref "Q7") (pin "3") (pinfunction "C_3") (pintype "passive"))
    )
    (net (code "69") (name "Net-(Q8-B)") (class "Default")
      (node (ref "Q8") (pin "1") (pinfunction "B_1") (pintype "passive"))
      (node (ref "R21") (pin "2") (pinfunction "2_2") (pintype "passive"))
    )
    (net (code "70") (name "Net-(R17-TAP)") (class "Default")
      (node (ref "R17") (pin "3") (pinfunction "TAP_3") (pintype "passive"))
      (node (ref "U3") (pin "2") (pinfunction "IN-_2") (pintype "input"))
    )
    (net (code "71") (name "Net-(U1-C1+)") (class "Default")
      (node (ref "C2") (pin "1") (pinfunction "1_1") (pintype "passive"))
      (node (ref "U1") (pin "1") (pinfunction "C1+_1") (pintype "passive"))
    )
    (net (code "72") (name "Net-(U1-C1-)") (class "Default")
      (node (ref "C2") (pin "2") (pinfunction "2_2") (pintype "passive"))
      (node (ref "U1") (pin "3") (pinfunction "C1-_3") (pintype "passive"))
    )
    (net (code "73") (name "Net-(U1-C2+)") (class "Default")
      (node (ref "C5") (pin "1") (pinfunction "1_1") (pintype "passive"))
      (node (ref "U1") (pin "4") (pinfunction "C2+_4") (pintype "passive"))
    )
    (net (code "74") (name "Net-(U1-C2-)") (class "Default")
      (node (ref "C5") (pin "2") (pinfunction "2_2") (pintype "passive"))
      (node (ref "U1") (pin "5") (pinfunction "C2-_5") (pintype "passive"))
    )
    (net (code "75") (name "Net-(U1-R1IN)") (class "Default")
      (node (ref "J1") (pin "3") (pinfunction "3_3") (pintype "passive"))
      (node (ref "U1") (pin "13") (pinfunction "R1IN_13") (pintype "passive"))
    )
    (net (code "76") (name "Net-(U1-T1OUT)") (class "Default")
      (node (ref "J1") (pin "2") (pinfunction "2_2") (pintype "passive"))
      (node (ref "U1") (pin "14") (pinfunction "T1OUT_14") (pintype "passive"))
    )
    (net (code "77") (name "Net-(U1-V+)") (class "Default")
      (node (ref "C3") (pin "1") (pinfunction "1_1") (pintype "passive"))
      (node (ref "U1") (pin "2") (pinfunction "V+_2") (pintype "passive"))
    )
    (net (code "78") (name "Net-(U1-V-)") (class "Default")
      (node (ref "C6") (pin "2") (pinfunction "2_2") (pintype "passive"))
      (node (ref "U1") (pin "6") (pinfunction "V-_6") (pintype "passive"))
    )
    (net (code "79") (name "Net-(U3A-IN+)") (class "Default")
      (node (ref "R18") (pin "1") (pinfunction "1_1") (pintype "passive"))
      (node (ref "U3") (pin "3") (pinfunction "IN+_3") (pintype "input"))
      (node (ref "光敏器件1") (pin "1") (pinfunction "1_1") (pintype "passive"))
    )
    (net (code "80") (name "VCC") (class "Default")
      (node (ref "+1") (pin "1") (pinfunction "1_1") (pintype "passive"))
      (node (ref "+1") (pin "2") (pinfunction "2_2") (pintype "passive"))
      (node (ref "+1") (pin "3") (pinfunction "3_3") (pintype "passive"))
      (node (ref "+1") (pin "4") (pinfunction "4_4") (pintype "passive"))
      (node (ref "1") (pin "2") (pinfunction "2_2") (pintype "passive"))
      (node (ref "C1") (pin "1") (pinfunction "1_1") (pintype "passive"))
      (node (ref "C3") (pin "2") (pinfunction "2_2") (pintype "passive"))
      (node (ref "C4") (pin "1") (pinfunction "1_1") (pintype "passive"))
      (node (ref "C7") (pin "1") (pinfunction "1_1") (pintype "passive"))
      (node (ref "KEY1") (pin "2") (pinfunction "NO1_2") (pintype "passive"))
      (node (ref "Q1") (pin "2") (pinfunction "E_2") (pintype "passive"))
      (node (ref "Q2") (pin "2") (pinfunction "E_2") (pintype "passive"))
      (node (ref "Q3") (pin "2") (pinfunction "E_2") (pintype "passive"))
      (node (ref "Q4") (pin "2") (pinfunction "E_2") (pintype "passive"))
      (node (ref "Q5") (pin "2") (pinfunction "E_2") (pintype "passive"))
      (node (ref "Q6") (pin "2") (pinfunction "E_2") (pintype "passive"))
      (node (ref "Q7") (pin "2") (pinfunction "E_2") (pintype "passive"))
      (node (ref "Q8") (pin "2") (pinfunction "E_2") (pintype "passive"))
      (node (ref "R1") (pin "1") (pinfunction "1_1") (pintype "passive"))
      (node (ref "R16") (pin "2") (pinfunction "2_2") (pintype "passive"))
      (node (ref "R17") (pin "1") (pinfunction "TOP_1") (pintype "passive"))
      (node (ref "R18") (pin "2") (pinfunction "2_2") (pintype "passive"))
      (node (ref "S1") (pin "2") (pinfunction "2_2") (pintype "passive"))
      (node (ref "U1") (pin "16") (pinfunction "VCC_16") (pintype "passive"))
      (node (ref "U2") (pin "31") (pinfunction "~{EA}_31") (pintype "input"))
      (node (ref "U2") (pin "40") (pinfunction "VCC_40") (pintype "power_in"))
      (node (ref "U3") (pin "8") (pinfunction "V+_8") (pintype "power_in"))
    )
    (net (code "81") (name "unconnected-(1-Pad3)") (class "Default")
      (node (ref "1") (pin "3") (pinfunction "3_3") (pintype "passive"))
    )
    (net (code "82") (name "unconnected-(1-Pad9)") (class "Default")
      (node (ref "1") (pin "9") (pinfunction "9_9") (pintype "passive"))
    )
    (net (code "83") (name "unconnected-(DS1-A-Pad3)") (class "Default")
      (node (ref "DS1") (pin "3") (pinfunction "A_3") (pintype "passive"))
    )
    (net (code "84") (name "unconnected-(DS2-A-Pad3)") (class "Default")
      (node (ref "DS2") (pin "3") (pinfunction "A_3") (pintype "passive"))
    )
    (net (code "85") (name "unconnected-(DS3-A-Pad3)") (class "Default")
      (node (ref "DS3") (pin "3") (pinfunction "A_3") (pintype "passive"))
    )
    (net (code "86") (name "unconnected-(DS4-A-Pad3)") (class "Default")
      (node (ref "DS4") (pin "3") (pinfunction "A_3") (pintype "passive"))
    )
    (net (code "87") (name "unconnected-(DS5-A-Pad3)") (class "Default")
      (node (ref "DS5") (pin "3") (pinfunction "A_3") (pintype "passive"))
    )
    (net (code "88") (name "unconnected-(DS6-A-Pad3)") (class "Default")
      (node (ref "DS6") (pin "3") (pinfunction "A_3") (pintype "passive"))
    )
    (net (code "89") (name "unconnected-(J1-MH1-Pad10)") (class "Default")
      (node (ref "J1") (pin "10") (pinfunction "MH1_10") (pintype "passive"))
    )
    (net (code "90") (name "unconnected-(J1-MH2-Pad11)") (class "Default")
      (node (ref "J1") (pin "11") (pinfunction "MH2_11") (pintype "passive"))
    )
    (net (code "91") (name "unconnected-(J1-Pad1)") (class "Default")
      (node (ref "J1") (pin "1") (pinfunction "1_1") (pintype "passive"))
    )
    (net (code "92") (name "unconnected-(J1-Pad4)") (class "Default")
      (node (ref "J1") (pin "4") (pinfunction "4_4") (pintype "passive"))
    )
    (net (code "93") (name "unconnected-(J1-Pad6)") (class "Default")
      (node (ref "J1") (pin "6") (pinfunction "6_6") (pintype "passive"))
    )
    (net (code "94") (name "unconnected-(J1-Pad7)") (class "Default")
      (node (ref "J1") (pin "7") (pinfunction "7_7") (pintype "passive"))
    )
    (net (code "95") (name "unconnected-(J1-Pad8)") (class "Default")
      (node (ref "J1") (pin "8") (pinfunction "8_8") (pintype "passive"))
    )
    (net (code "96") (name "unconnected-(J1-Pad9)") (class "Default")
      (node (ref "J1") (pin "9") (pinfunction "9_9") (pintype "passive"))
    )
    (net (code "97") (name "unconnected-(U1-R2IN-Pad8)") (class "Default")
      (node (ref "U1") (pin "8") (pinfunction "R2IN_8") (pintype "passive"))
    )
    (net (code "98") (name "unconnected-(U1-R2OUT-Pad9)") (class "Default")
      (node (ref "U1") (pin "9") (pinfunction "R2OUT_9") (pintype "passive"))
    )
    (net (code "99") (name "unconnected-(U1-T2IN-Pad10)") (class "Default")
      (node (ref "U1") (pin "10") (pinfunction "T2IN_10") (pintype "passive"))
    )
    (net (code "100") (name "unconnected-(U1-T2OUT-Pad7)") (class "Default")
      (node (ref "U1") (pin "7") (pinfunction "T2OUT_7") (pintype "passive"))
    )
  )
)
